# TMR1_v2.net
KiCad netlist of a schematic drawn in EAGLE
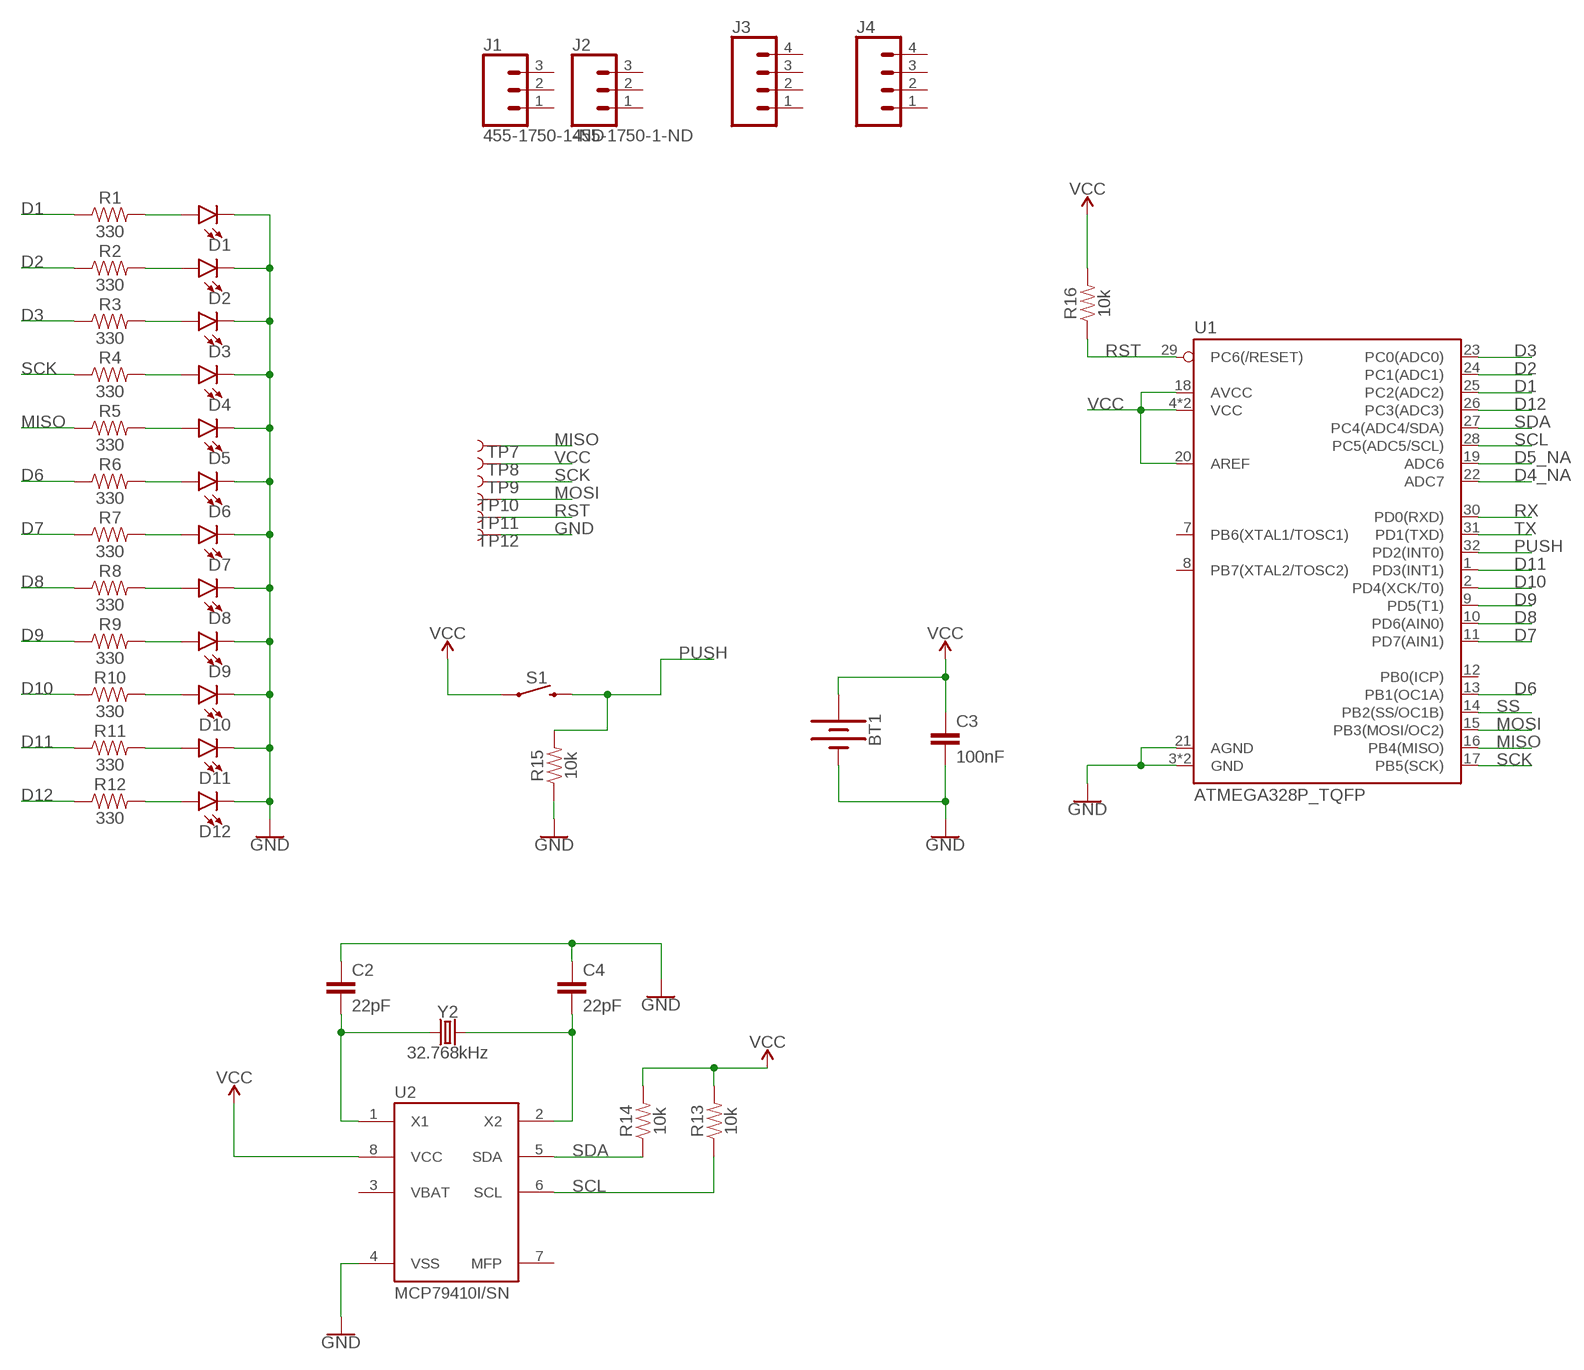
[diagram p0: schematic, sheet 1]

(export (version "E")
  (design (tool "Eeschema 10.0.6"))
  (components
    (comp (ref "BT1")
      (value "BATTERY-20MM_SMD_4LEGS")
      (footprint "eagle-import:BATTCON_20MM_4LEGS")
      (libsource (lib "eagle-import") (part "BATTERY-20MM_SMD_4LEGS"))
    )
    (comp (ref "C2")
      (value "22pF")
      (footprint "eagle-import:0603")
      (libsource (lib "eagle-import") (part "22PF-0603-50V-5%"))
    )
    (comp (ref "C3")
      (value "100nF")
      (footprint "eagle-import:0603")
      (libsource (lib "eagle-import") (part "22PF-0603-50V-5%"))
    )
    (comp (ref "C4")
      (value "22pF")
      (footprint "eagle-import:0603")
      (libsource (lib "eagle-import") (part "22PF-0603-50V-5%"))
    )
    (comp (ref "D1")
      (value "LED0603")
      (footprint "eagle-import:LED-0603")
      (libsource (lib "eagle-import") (part "LED0603"))
    )
    (comp (ref "D2")
      (value "LED0603")
      (footprint "eagle-import:LED-0603")
      (libsource (lib "eagle-import") (part "LED0603"))
    )
    (comp (ref "D3")
      (value "LED0603")
      (footprint "eagle-import:LED-0603")
      (libsource (lib "eagle-import") (part "LED0603"))
    )
    (comp (ref "D4")
      (value "LED0603")
      (footprint "eagle-import:LED-0603")
      (libsource (lib "eagle-import") (part "LED0603"))
    )
    (comp (ref "D5")
      (value "LED0603")
      (footprint "eagle-import:LED-0603")
      (libsource (lib "eagle-import") (part "LED0603"))
    )
    (comp (ref "D6")
      (value "LED0603")
      (footprint "eagle-import:LED-0603")
      (libsource (lib "eagle-import") (part "LED0603"))
    )
    (comp (ref "D7")
      (value "LED0603")
      (footprint "eagle-import:LED-0603")
      (libsource (lib "eagle-import") (part "LED0603"))
    )
    (comp (ref "D8")
      (value "LED0603")
      (footprint "eagle-import:LED-0603")
      (libsource (lib "eagle-import") (part "LED0603"))
    )
    (comp (ref "D9")
      (value "LED0603")
      (footprint "eagle-import:LED-0603")
      (libsource (lib "eagle-import") (part "LED0603"))
    )
    (comp (ref "D10")
      (value "LED0603")
      (footprint "eagle-import:LED-0603")
      (libsource (lib "eagle-import") (part "LED0603"))
    )
    (comp (ref "D11")
      (value "LED0603")
      (footprint "eagle-import:LED-0603")
      (libsource (lib "eagle-import") (part "LED0603"))
    )
    (comp (ref "D12")
      (value "LED0603")
      (footprint "eagle-import:LED-0603")
      (libsource (lib "eagle-import") (part "LED0603"))
    )
    (comp (ref "J1")
      (value "455-1750-1-ND")
      (footprint "eagle-import:1X03")
      (libsource (lib "eagle-import") (part "CONN_03"))
    )
    (comp (ref "J2")
      (value "455-1750-1-ND")
      (footprint "eagle-import:1X03")
      (libsource (lib "eagle-import") (part "CONN_03"))
    )
    (comp (ref "J3")
      (value "CONN_04")
      (footprint "eagle-import:1X04")
      (libsource (lib "eagle-import") (part "CONN_04"))
    )
    (comp (ref "J4")
      (value "CONN_04")
      (footprint "eagle-import:1X04")
      (libsource (lib "eagle-import") (part "CONN_04"))
    )
    (comp (ref "R1")
      (value "330")
      (footprint "eagle-import:0603")
      (libsource (lib "eagle-import") (part "330OHM-0603-1/10W-1%"))
    )
    (comp (ref "R2")
      (value "330")
      (footprint "eagle-import:0603")
      (libsource (lib "eagle-import") (part "330OHM-0603-1/10W-1%"))
    )
    (comp (ref "R3")
      (value "330")
      (footprint "eagle-import:0603")
      (libsource (lib "eagle-import") (part "330OHM-0603-1/10W-1%"))
    )
    (comp (ref "R4")
      (value "330")
      (footprint "eagle-import:0603")
      (libsource (lib "eagle-import") (part "330OHM-0603-1/10W-1%"))
    )
    (comp (ref "R5")
      (value "330")
      (footprint "eagle-import:0603")
      (libsource (lib "eagle-import") (part "330OHM-0603-1/10W-1%"))
    )
    (comp (ref "R6")
      (value "330")
      (footprint "eagle-import:0603")
      (libsource (lib "eagle-import") (part "330OHM-0603-1/10W-1%"))
    )
    (comp (ref "R7")
      (value "330")
      (footprint "eagle-import:0603")
      (libsource (lib "eagle-import") (part "330OHM-0603-1/10W-1%"))
    )
    (comp (ref "R8")
      (value "330")
      (footprint "eagle-import:0603")
      (libsource (lib "eagle-import") (part "330OHM-0603-1/10W-1%"))
    )
    (comp (ref "R9")
      (value "330")
      (footprint "eagle-import:0603")
      (libsource (lib "eagle-import") (part "330OHM-0603-1/10W-1%"))
    )
    (comp (ref "R10")
      (value "330")
      (footprint "eagle-import:0603")
      (libsource (lib "eagle-import") (part "330OHM-0603-1/10W-1%"))
    )
    (comp (ref "R11")
      (value "330")
      (footprint "eagle-import:0603")
      (libsource (lib "eagle-import") (part "330OHM-0603-1/10W-1%"))
    )
    (comp (ref "R12")
      (value "330")
      (footprint "eagle-import:0603")
      (libsource (lib "eagle-import") (part "330OHM-0603-1/10W-1%"))
    )
    (comp (ref "R13")
      (value "10k")
      (footprint "eagle-import:0603")
      (libsource (lib "eagle-import") (part "10KOHM-0603-1/10W-1%"))
    )
    (comp (ref "R14")
      (value "10k")
      (footprint "eagle-import:0603")
      (libsource (lib "eagle-import") (part "10KOHM-0603-1/10W-1%"))
    )
    (comp (ref "R15")
      (value "10k")
      (footprint "eagle-import:0603")
      (libsource (lib "eagle-import") (part "10KOHM-0603-1/10W-1%"))
    )
    (comp (ref "R16")
      (value "10k")
      (footprint "eagle-import:0603")
      (libsource (lib "eagle-import") (part "10KOHM-0603-1/10W-1%"))
    )
    (comp (ref "S1")
      (value "MOMENTARY-SWITCH-SPST-SMD-5.2MM")
      (footprint "eagle-import:TACTILE_SWITCH_SMD_5.2MM")
      (libsource (lib "eagle-import") (part "MOMENTARY-SWITCH-SPST-SMD-5.2MM"))
    )
    (comp (ref "TP7")
      (value "TEST-POINT3X4")
      (footprint "eagle-import:PAD.03X.04")
      (libsource (lib "eagle-import") (part "TEST-POINT3X4"))
    )
    (comp (ref "TP8")
      (value "TEST-POINT3X4")
      (footprint "eagle-import:PAD.03X.04")
      (libsource (lib "eagle-import") (part "TEST-POINT3X4"))
    )
    (comp (ref "TP9")
      (value "TEST-POINT3X4")
      (footprint "eagle-import:PAD.03X.04")
      (libsource (lib "eagle-import") (part "TEST-POINT3X4"))
    )
    (comp (ref "TP10")
      (value "TEST-POINT3X4")
      (footprint "eagle-import:PAD.03X.04")
      (libsource (lib "eagle-import") (part "TEST-POINT3X4"))
    )
    (comp (ref "TP11")
      (value "TEST-POINT3X4")
      (footprint "eagle-import:PAD.03X.04")
      (libsource (lib "eagle-import") (part "TEST-POINT3X4"))
    )
    (comp (ref "TP12")
      (value "TEST-POINT3X4")
      (footprint "eagle-import:PAD.03X.04")
      (libsource (lib "eagle-import") (part "TEST-POINT3X4"))
    )
    (comp (ref "U1")
      (value "ATMEGA328P_TQFP")
      (footprint "eagle-import:TQFP32-08")
      (libsource (lib "eagle-import") (part "ATMEGA328P_TQFP"))
    )
    (comp (ref "U2")
      (value "MCP79410I/SN")
      (footprint "eagle-import:SO8")
      (libsource (lib "eagle-import") (part "MCP7941?/SN0I"))
    )
    (comp (ref "Y2")
      (value "32.768kHz")
      (footprint "eagle-import:CRYSTAL-PTH-2X6-CYL")
      (libsource (lib "eagle-import") (part "CRYSTAL-32.768KHZPTH-2X6"))
    )
  )
  (nets
    (net (code "1") (name "/D1") (class "Default")
      (node (ref "R1") (pin "1") (pinfunction "1_1") (pintype "passive"))
      (node (ref "U1") (pin "25") (pinfunction "PC2(ADC2)_25") (pintype "bidirectional"))
    )
    (net (code "2") (name "/D2") (class "Default")
      (node (ref "R2") (pin "1") (pinfunction "1_1") (pintype "passive"))
      (node (ref "U1") (pin "24") (pinfunction "PC1(ADC1)_24") (pintype "bidirectional"))
    )
    (net (code "3") (name "/D3") (class "Default")
      (node (ref "R3") (pin "1") (pinfunction "1_1") (pintype "passive"))
      (node (ref "U1") (pin "23") (pinfunction "PC0(ADC0)_23") (pintype "bidirectional"))
    )
    (net (code "4") (name "/D4_NA") (class "Default")
      (node (ref "U1") (pin "22") (pinfunction "ADC7_22") (pintype "bidirectional"))
    )
    (net (code "5") (name "/D5_NA") (class "Default")
      (node (ref "U1") (pin "19") (pinfunction "ADC6_19") (pintype "bidirectional"))
    )
    (net (code "6") (name "/D6") (class "Default")
      (node (ref "R6") (pin "1") (pinfunction "1_1") (pintype "passive"))
      (node (ref "U1") (pin "13") (pinfunction "PB1(OC1A)_13") (pintype "bidirectional"))
    )
    (net (code "7") (name "/D7") (class "Default")
      (node (ref "R7") (pin "1") (pinfunction "1_1") (pintype "passive"))
      (node (ref "U1") (pin "11") (pinfunction "PD7(AIN1)_11") (pintype "bidirectional"))
    )
    (net (code "8") (name "/D8") (class "Default")
      (node (ref "R8") (pin "1") (pinfunction "1_1") (pintype "passive"))
      (node (ref "U1") (pin "10") (pinfunction "PD6(AIN0)_10") (pintype "bidirectional"))
    )
    (net (code "9") (name "/D9") (class "Default")
      (node (ref "R9") (pin "1") (pinfunction "1_1") (pintype "passive"))
      (node (ref "U1") (pin "9") (pinfunction "PD5(T1)_9") (pintype "bidirectional"))
    )
    (net (code "10") (name "/D10") (class "Default")
      (node (ref "R10") (pin "1") (pinfunction "1_1") (pintype "passive"))
      (node (ref "U1") (pin "2") (pinfunction "PD4(XCK/T0)_2") (pintype "bidirectional"))
    )
    (net (code "11") (name "/D11") (class "Default")
      (node (ref "R11") (pin "1") (pinfunction "1_1") (pintype "passive"))
      (node (ref "U1") (pin "1") (pinfunction "PD3(INT1)_1") (pintype "bidirectional"))
    )
    (net (code "12") (name "/D12") (class "Default")
      (node (ref "R12") (pin "1") (pinfunction "1_1") (pintype "passive"))
      (node (ref "U1") (pin "26") (pinfunction "PC3(ADC3)_26") (pintype "bidirectional"))
    )
    (net (code "13") (name "/MISO") (class "Default")
      (node (ref "R5") (pin "1") (pinfunction "1_1") (pintype "passive"))
      (node (ref "TP7") (pin "P$1") (pinfunction "1_P$1") (pintype "bidirectional"))
      (node (ref "U1") (pin "16") (pinfunction "PB4(MISO)_16") (pintype "bidirectional"))
    )
    (net (code "14") (name "/MOSI") (class "Default")
      (node (ref "TP10") (pin "P$1") (pinfunction "1_P$1") (pintype "bidirectional"))
      (node (ref "U1") (pin "15") (pinfunction "PB3(MOSI/OC2)_15") (pintype "bidirectional"))
    )
    (net (code "15") (name "/PUSH") (class "Default")
      (node (ref "R15") (pin "2") (pinfunction "2_2") (pintype "passive"))
      (node (ref "S1") (pin "3") (pinfunction "2_3") (pintype "passive"))
      (node (ref "U1") (pin "32") (pinfunction "PD2(INT0)_32") (pintype "bidirectional"))
    )
    (net (code "16") (name "/RST") (class "Default")
      (node (ref "R16") (pin "1") (pinfunction "1_1") (pintype "passive"))
      (node (ref "TP11") (pin "P$1") (pinfunction "1_P$1") (pintype "bidirectional"))
      (node (ref "U1") (pin "29") (pinfunction "PC6(/RESET)_29") (pintype "bidirectional"))
    )
    (net (code "17") (name "/RX") (class "Default")
      (node (ref "U1") (pin "30") (pinfunction "PD0(RXD)_30") (pintype "bidirectional"))
    )
    (net (code "18") (name "/SCK") (class "Default")
      (node (ref "R4") (pin "1") (pinfunction "1_1") (pintype "passive"))
      (node (ref "TP9") (pin "P$1") (pinfunction "1_P$1") (pintype "bidirectional"))
      (node (ref "U1") (pin "17") (pinfunction "PB5(SCK)_17") (pintype "bidirectional"))
    )
    (net (code "19") (name "/SCL") (class "Default")
      (node (ref "R13") (pin "1") (pinfunction "1_1") (pintype "passive"))
      (node (ref "U1") (pin "28") (pinfunction "PC5(ADC5/SCL)_28") (pintype "bidirectional"))
      (node (ref "U2") (pin "6") (pinfunction "SCL_6") (pintype "input"))
    )
    (net (code "20") (name "/SDA") (class "Default")
      (node (ref "R14") (pin "1") (pinfunction "1_1") (pintype "passive"))
      (node (ref "U1") (pin "27") (pinfunction "PC4(ADC4/SDA)_27") (pintype "bidirectional"))
      (node (ref "U2") (pin "5") (pinfunction "SDA_5") (pintype "open_collector"))
    )
    (net (code "21") (name "/SS") (class "Default")
      (node (ref "U1") (pin "14") (pinfunction "PB2(SS/OC1B)_14") (pintype "bidirectional"))
    )
    (net (code "22") (name "/TX") (class "Default")
      (node (ref "U1") (pin "31") (pinfunction "PD1(TXD)_31") (pintype "bidirectional"))
    )
    (net (code "23") (name "/VBAT") (class "Default")
      (node (ref "U2") (pin "3") (pinfunction "VBAT_3") (pintype "power_in"))
    )
    (net (code "24") (name "GND") (class "Default")
      (node (ref "BT1") (pin "NEGATIVE") (pinfunction "-_NEGATIVE") (pintype "power_in"))
      (node (ref "C2") (pin "1") (pinfunction "1_1") (pintype "passive"))
      (node (ref "C3") (pin "2") (pinfunction "2_2") (pintype "passive"))
      (node (ref "C4") (pin "1") (pinfunction "1_1") (pintype "passive"))
      (node (ref "D1") (pin "C") (pinfunction "C_C") (pintype "passive"))
      (node (ref "D10") (pin "C") (pinfunction "C_C") (pintype "passive"))
      (node (ref "D11") (pin "C") (pinfunction "C_C") (pintype "passive"))
      (node (ref "D12") (pin "C") (pinfunction "C_C") (pintype "passive"))
      (node (ref "D2") (pin "C") (pinfunction "C_C") (pintype "passive"))
      (node (ref "D3") (pin "C") (pinfunction "C_C") (pintype "passive"))
      (node (ref "D4") (pin "C") (pinfunction "C_C") (pintype "passive"))
      (node (ref "D5") (pin "C") (pinfunction "C_C") (pintype "passive"))
      (node (ref "D6") (pin "C") (pinfunction "C_C") (pintype "passive"))
      (node (ref "D7") (pin "C") (pinfunction "C_C") (pintype "passive"))
      (node (ref "D8") (pin "C") (pinfunction "C_C") (pintype "passive"))
      (node (ref "D9") (pin "C") (pinfunction "C_C") (pintype "passive"))
      (node (ref "R15") (pin "1") (pinfunction "1_1") (pintype "passive"))
      (node (ref "TP12") (pin "P$1") (pinfunction "1_P$1") (pintype "bidirectional"))
      (node (ref "U1") (pin "21") (pinfunction "AGND_21") (pintype "bidirectional"))
      (node (ref "U1") (pin "3") (pinfunction "GND_3") (pintype "bidirectional"))
      (node (ref "U1") (pin "5") (pinfunction "GND_5") (pintype "bidirectional"))
      (node (ref "U2") (pin "4") (pinfunction "VSS_4") (pintype "power_in"))
    )
    (net (code "25") (name "Net-(D1-PadA)") (class "Default")
      (node (ref "D1") (pin "A") (pinfunction "A_A") (pintype "passive"))
      (node (ref "R1") (pin "2") (pinfunction "2_2") (pintype "passive"))
    )
    (net (code "26") (name "Net-(D2-PadA)") (class "Default")
      (node (ref "D2") (pin "A") (pinfunction "A_A") (pintype "passive"))
      (node (ref "R2") (pin "2") (pinfunction "2_2") (pintype "passive"))
    )
    (net (code "27") (name "Net-(D3-PadA)") (class "Default")
      (node (ref "D3") (pin "A") (pinfunction "A_A") (pintype "passive"))
      (node (ref "R3") (pin "2") (pinfunction "2_2") (pintype "passive"))
    )
    (net (code "28") (name "Net-(D4-PadA)") (class "Default")
      (node (ref "D4") (pin "A") (pinfunction "A_A") (pintype "passive"))
      (node (ref "R4") (pin "2") (pinfunction "2_2") (pintype "passive"))
    )
    (net (code "29") (name "Net-(D5-PadA)") (class "Default")
      (node (ref "D5") (pin "A") (pinfunction "A_A") (pintype "passive"))
      (node (ref "R5") (pin "2") (pinfunction "2_2") (pintype "passive"))
    )
    (net (code "30") (name "Net-(D6-PadA)") (class "Default")
      (node (ref "D6") (pin "A") (pinfunction "A_A") (pintype "passive"))
      (node (ref "R6") (pin "2") (pinfunction "2_2") (pintype "passive"))
    )
    (net (code "31") (name "Net-(D7-PadA)") (class "Default")
      (node (ref "D7") (pin "A") (pinfunction "A_A") (pintype "passive"))
      (node (ref "R7") (pin "2") (pinfunction "2_2") (pintype "passive"))
    )
    (net (code "32") (name "Net-(D8-PadA)") (class "Default")
      (node (ref "D8") (pin "A") (pinfunction "A_A") (pintype "passive"))
      (node (ref "R8") (pin "2") (pinfunction "2_2") (pintype "passive"))
    )
    (net (code "33") (name "Net-(D9-PadA)") (class "Default")
      (node (ref "D9") (pin "A") (pinfunction "A_A") (pintype "passive"))
      (node (ref "R9") (pin "2") (pinfunction "2_2") (pintype "passive"))
    )
    (net (code "34") (name "Net-(D10-PadA)") (class "Default")
      (node (ref "D10") (pin "A") (pinfunction "A_A") (pintype "passive"))
      (node (ref "R10") (pin "2") (pinfunction "2_2") (pintype "passive"))
    )
    (net (code "35") (name "Net-(D11-PadA)") (class "Default")
      (node (ref "D11") (pin "A") (pinfunction "A_A") (pintype "passive"))
      (node (ref "R11") (pin "2") (pinfunction "2_2") (pintype "passive"))
    )
    (net (code "36") (name "Net-(D12-PadA)") (class "Default")
      (node (ref "D12") (pin "A") (pinfunction "A_A") (pintype "passive"))
      (node (ref "R12") (pin "2") (pinfunction "2_2") (pintype "passive"))
    )
    (net (code "37") (name "Net-(U2-X1)") (class "Default")
      (node (ref "C2") (pin "2") (pinfunction "2_2") (pintype "passive"))
      (node (ref "U2") (pin "1") (pinfunction "X1_1") (pintype "input"))
      (node (ref "Y2") (pin "1") (pinfunction "1_1") (pintype "passive"))
    )
    (net (code "38") (name "Net-(U2-X2)") (class "Default")
      (node (ref "C4") (pin "2") (pinfunction "2_2") (pintype "passive"))
      (node (ref "U2") (pin "2") (pinfunction "X2_2") (pintype "output"))
      (node (ref "Y2") (pin "2") (pinfunction "2_2") (pintype "passive"))
    )
    (net (code "39") (name "VCC") (class "Default")
      (node (ref "BT1") (pin "POSITIVE@1") (pinfunction "+_POSITIVE@1") (pintype "power_in"))
      (node (ref "BT1") (pin "POSITIVE@2") (pinfunction "+_POSITIVE@2") (pintype "power_in"))
      (node (ref "BT1") (pin "POSITIVE@3") (pinfunction "+_POSITIVE@3") (pintype "power_in"))
      (node (ref "BT1") (pin "POSITIVE@4") (pinfunction "+_POSITIVE@4") (pintype "power_in"))
      (node (ref "C3") (pin "1") (pinfunction "1_1") (pintype "passive"))
      (node (ref "R13") (pin "2") (pinfunction "2_2") (pintype "passive"))
      (node (ref "R14") (pin "2") (pinfunction "2_2") (pintype "passive"))
      (node (ref "R16") (pin "2") (pinfunction "2_2") (pintype "passive"))
      (node (ref "S1") (pin "1") (pinfunction "1_1") (pintype "passive"))
      (node (ref "TP8") (pin "P$1") (pinfunction "1_P$1") (pintype "bidirectional"))
      (node (ref "U1") (pin "18") (pinfunction "AVCC_18") (pintype "bidirectional"))
      (node (ref "U1") (pin "20") (pinfunction "AREF_20") (pintype "bidirectional"))
      (node (ref "U1") (pin "4") (pinfunction "VCC_4") (pintype "bidirectional"))
      (node (ref "U1") (pin "6") (pinfunction "VCC_6") (pintype "bidirectional"))
      (node (ref "U2") (pin "8") (pinfunction "VCC_8") (pintype "power_in"))
    )
    (net (code "40") (name "unconnected-(J1-Pad1)") (class "Default")
      (node (ref "J1") (pin "1") (pinfunction "1_1") (pintype "passive"))
    )
    (net (code "41") (name "unconnected-(J1-Pad2)") (class "Default")
      (node (ref "J1") (pin "2") (pinfunction "2_2") (pintype "passive"))
    )
    (net (code "42") (name "unconnected-(J1-Pad3)") (class "Default")
      (node (ref "J1") (pin "3") (pinfunction "3_3") (pintype "passive"))
    )
    (net (code "43") (name "unconnected-(J2-Pad1)") (class "Default")
      (node (ref "J2") (pin "1") (pinfunction "1_1") (pintype "passive"))
    )
    (net (code "44") (name "unconnected-(J2-Pad2)") (class "Default")
      (node (ref "J2") (pin "2") (pinfunction "2_2") (pintype "passive"))
    )
    (net (code "45") (name "unconnected-(J2-Pad3)") (class "Default")
      (node (ref "J2") (pin "3") (pinfunction "3_3") (pintype "passive"))
    )
    (net (code "46") (name "unconnected-(J3-Pad1)") (class "Default")
      (node (ref "J3") (pin "1") (pinfunction "1_1") (pintype "passive"))
    )
    (net (code "47") (name "unconnected-(J3-Pad2)") (class "Default")
      (node (ref "J3") (pin "2") (pinfunction "2_2") (pintype "passive"))
    )
    (net (code "48") (name "unconnected-(J3-Pad3)") (class "Default")
      (node (ref "J3") (pin "3") (pinfunction "3_3") (pintype "passive"))
    )
    (net (code "49") (name "unconnected-(J3-Pad4)") (class "Default")
      (node (ref "J3") (pin "4") (pinfunction "4_4") (pintype "passive"))
    )
    (net (code "50") (name "unconnected-(J4-Pad1)") (class "Default")
      (node (ref "J4") (pin "1") (pinfunction "1_1") (pintype "passive"))
    )
    (net (code "51") (name "unconnected-(J4-Pad2)") (class "Default")
      (node (ref "J4") (pin "2") (pinfunction "2_2") (pintype "passive"))
    )
    (net (code "52") (name "unconnected-(J4-Pad3)") (class "Default")
      (node (ref "J4") (pin "3") (pinfunction "3_3") (pintype "passive"))
    )
    (net (code "53") (name "unconnected-(J4-Pad4)") (class "Default")
      (node (ref "J4") (pin "4") (pinfunction "4_4") (pintype "passive"))
    )
    (net (code "54") (name "unconnected-(U1-PB0(ICP)-Pad12)") (class "Default")
      (node (ref "U1") (pin "12") (pinfunction "PB0(ICP)_12") (pintype "bidirectional"))
    )
    (net (code "55") (name "unconnected-(U1-PB6(XTAL1{slash}TOSC1)-Pad7)") (class "Default")
      (node (ref "U1") (pin "7") (pinfunction "PB6(XTAL1/TOSC1)_7") (pintype "bidirectional"))
    )
    (net (code "56") (name "unconnected-(U1-PB7(XTAL2{slash}TOSC2)-Pad8)") (class "Default")
      (node (ref "U1") (pin "8") (pinfunction "PB7(XTAL2/TOSC2)_8") (pintype "bidirectional"))
    )
    (net (code "57") (name "unconnected-(U2-MFP-Pad7)") (class "Default")
      (node (ref "U2") (pin "7") (pinfunction "MFP_7") (pintype "open_collector"))
    )
  )
)
